# PID.net
KiCad netlist of a schematic drawn in EAGLE
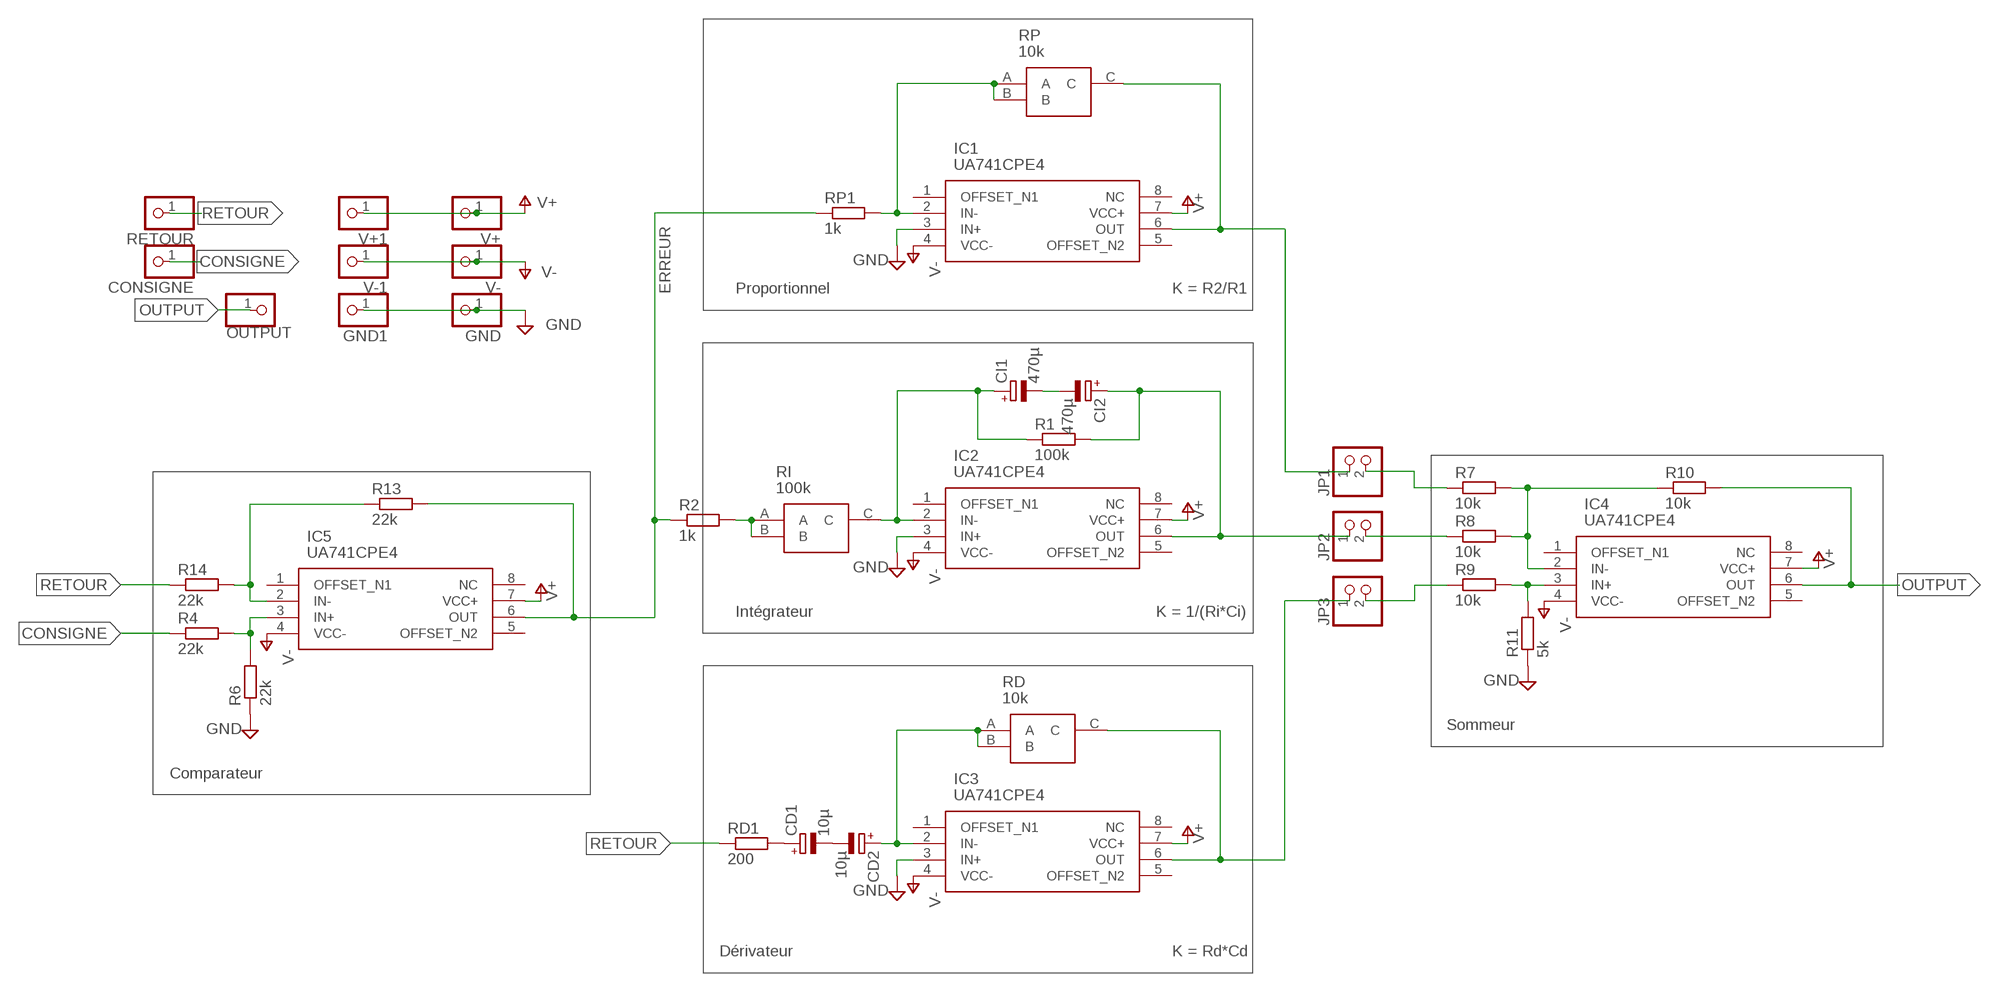
[diagram p0: schematic, sheet 1]

(export (version "E")
  (design (tool "Eeschema 10.0.6"))
  (components
    (comp (ref "CD1")
      (value "10µ")
      (footprint "eagle-import:E2,5-6")
      (libsource (lib "eagle-import") (part "CPOL-EUE2.5-6"))
    )
    (comp (ref "CD2")
      (value "10µ")
      (footprint "eagle-import:E2,5-6")
      (libsource (lib "eagle-import") (part "CPOL-EUE2.5-6"))
    )
    (comp (ref "CI1")
      (value "470µ")
      (footprint "eagle-import:E2,5-6")
      (libsource (lib "eagle-import") (part "CPOL-EUE2.5-6"))
    )
    (comp (ref "CI2")
      (value "470µ")
      (footprint "eagle-import:E2,5-6")
      (libsource (lib "eagle-import") (part "CPOL-EUE2.5-6"))
    )
    (comp (ref "CONSIGNE")
      (value "PINHD-1X1")
      (footprint "eagle-import:1X01")
      (libsource (lib "eagle-import") (part "PINHD-1X1"))
    )
    (comp (ref "GND")
      (value "PINHD-1X1")
      (footprint "eagle-import:1X01")
      (libsource (lib "eagle-import") (part "PINHD-1X1"))
    )
    (comp (ref "GND1")
      (value "PINHD-1X1")
      (footprint "eagle-import:1X01")
      (libsource (lib "eagle-import") (part "PINHD-1X1"))
    )
    (comp (ref "IC1")
      (value "UA741CPE4")
      (footprint "eagle-import:DIP794W53P254L959H508Q8N")
      (fields
        (field (name "MOUSER_PART_NUMBER") "595-UA741CPE4")
        (field (name "SPICEMODEL") "OPAMP")
        (field (name "SPICEPREFIX") "X")
      )
      (libsource (lib "eagle-import") (part "UA741CPE4"))
    )
    (comp (ref "IC2")
      (value "UA741CPE4")
      (footprint "eagle-import:DIP794W53P254L959H508Q8N")
      (fields
        (field (name "MOUSER_PART_NUMBER") "595-UA741CPE4")
        (field (name "SPICEMODEL") "OPAMP")
        (field (name "SPICEPREFIX") "X")
      )
      (libsource (lib "eagle-import") (part "UA741CPE4"))
    )
    (comp (ref "IC3")
      (value "UA741CPE4")
      (footprint "eagle-import:DIP794W53P254L959H508Q8N")
      (fields
        (field (name "MOUSER_PART_NUMBER") "595-UA741CPE4")
        (field (name "SPICEMODEL") "OPAMP")
        (field (name "SPICEPREFIX") "X")
      )
      (libsource (lib "eagle-import") (part "UA741CPE4"))
    )
    (comp (ref "IC4")
      (value "UA741CPE4")
      (footprint "eagle-import:DIP794W53P254L959H508Q8N")
      (fields
        (field (name "MOUSER_PART_NUMBER") "595-UA741CPE4")
        (field (name "SPICEMODEL") "OPAMP")
        (field (name "SPICEPREFIX") "X")
      )
      (libsource (lib "eagle-import") (part "UA741CPE4"))
    )
    (comp (ref "IC5")
      (value "UA741CPE4")
      (footprint "eagle-import:DIP794W53P254L959H508Q8N")
      (fields
        (field (name "MOUSER_PART_NUMBER") "595-UA741CPE4")
        (field (name "SPICEMODEL") "OPAMP")
        (field (name "SPICEPREFIX") "X")
      )
      (libsource (lib "eagle-import") (part "UA741CPE4"))
    )
    (comp (ref "JP1")
      (value "PINHD-1X2")
      (footprint "eagle-import:1X02")
      (libsource (lib "eagle-import") (part "PINHD-1X2"))
    )
    (comp (ref "JP2")
      (value "PINHD-1X2")
      (footprint "eagle-import:1X02")
      (libsource (lib "eagle-import") (part "PINHD-1X2"))
    )
    (comp (ref "JP3")
      (value "PINHD-1X2")
      (footprint "eagle-import:1X02")
      (libsource (lib "eagle-import") (part "PINHD-1X2"))
    )
    (comp (ref "OUTPUT")
      (value "PINHD-1X1")
      (footprint "eagle-import:1X01")
      (libsource (lib "eagle-import") (part "PINHD-1X1"))
    )
    (comp (ref "R1")
      (value "100k")
      (footprint "eagle-import:0204_7")
      (libsource (lib "eagle-import") (part "R-EU_0204/7"))
    )
    (comp (ref "R2")
      (value "1k")
      (footprint "eagle-import:0204_7")
      (libsource (lib "eagle-import") (part "R-EU_0204/7"))
    )
    (comp (ref "R4")
      (value "22k")
      (footprint "eagle-import:0204_7")
      (libsource (lib "eagle-import") (part "R-EU_0204/7"))
    )
    (comp (ref "R6")
      (value "22k")
      (footprint "eagle-import:0204_7")
      (libsource (lib "eagle-import") (part "R-EU_0204/7"))
    )
    (comp (ref "R7")
      (value "10k")
      (footprint "eagle-import:0204_7")
      (libsource (lib "eagle-import") (part "R-EU_0204/7"))
    )
    (comp (ref "R8")
      (value "10k")
      (footprint "eagle-import:0204_7")
      (libsource (lib "eagle-import") (part "R-EU_0204/7"))
    )
    (comp (ref "R9")
      (value "10k")
      (footprint "eagle-import:0204_7")
      (libsource (lib "eagle-import") (part "R-EU_0204/7"))
    )
    (comp (ref "R10")
      (value "10k")
      (footprint "eagle-import:0204_7")
      (libsource (lib "eagle-import") (part "R-EU_0204/7"))
    )
    (comp (ref "R11")
      (value "5k")
      (footprint "eagle-import:0204_7")
      (libsource (lib "eagle-import") (part "R-EU_0204/7"))
    )
    (comp (ref "R13")
      (value "22k")
      (footprint "eagle-import:0204_7")
      (libsource (lib "eagle-import") (part "R-EU_0204/7"))
    )
    (comp (ref "R14")
      (value "22k")
      (footprint "eagle-import:0204_7")
      (libsource (lib "eagle-import") (part "R-EU_0204/7"))
    )
    (comp (ref "RD")
      (value "10k")
      (footprint "eagle-import:T7YA")
      (fields
        (field (name "MANUFACTURER_PART_NUMBER") "T7YA103MT20")
        (field (name "RS_PART_NUMBER") "3746787P")
      )
      (libsource (lib "eagle-import") (part "T7YA103MT20"))
    )
    (comp (ref "RD1")
      (value "200")
      (footprint "eagle-import:0204_7")
      (libsource (lib "eagle-import") (part "R-EU_0204/7"))
    )
    (comp (ref "RETOUR")
      (value "PINHD-1X1")
      (footprint "eagle-import:1X01")
      (libsource (lib "eagle-import") (part "PINHD-1X1"))
    )
    (comp (ref "RI")
      (value "100k")
      (footprint "eagle-import:T7YA")
      (fields
        (field (name "MANUFACTURER_PART_NUMBER") "T7YA103MT20")
        (field (name "RS_PART_NUMBER") "3746787P")
      )
      (libsource (lib "eagle-import") (part "T7YA103MT20"))
    )
    (comp (ref "RP")
      (value "10k")
      (footprint "eagle-import:T7YA")
      (fields
        (field (name "MANUFACTURER_PART_NUMBER") "T7YA103MT20")
        (field (name "RS_PART_NUMBER") "3746787P")
      )
      (libsource (lib "eagle-import") (part "T7YA103MT20"))
    )
    (comp (ref "RP1")
      (value "1k")
      (footprint "eagle-import:0204_7")
      (libsource (lib "eagle-import") (part "R-EU_0204/7"))
    )
    (comp (ref "V+")
      (value "PINHD-1X1")
      (footprint "eagle-import:1X01")
      (libsource (lib "eagle-import") (part "PINHD-1X1"))
    )
    (comp (ref "V+1")
      (value "PINHD-1X1")
      (footprint "eagle-import:1X01")
      (libsource (lib "eagle-import") (part "PINHD-1X1"))
    )
    (comp (ref "V-")
      (value "PINHD-1X1")
      (footprint "eagle-import:1X01")
      (libsource (lib "eagle-import") (part "PINHD-1X1"))
    )
    (comp (ref "V-1")
      (value "PINHD-1X1")
      (footprint "eagle-import:1X01")
      (libsource (lib "eagle-import") (part "PINHD-1X1"))
    )
  )
  (nets
    (net (code "1") (name "/ERREUR") (class "Default")
      (node (ref "IC5") (pin "6") (pinfunction "OUT_6") (pintype "output"))
      (node (ref "R13") (pin "2") (pinfunction "2_2") (pintype "passive"))
      (node (ref "R2") (pin "1") (pinfunction "1_1") (pintype "passive"))
      (node (ref "RP1") (pin "1") (pinfunction "1_1") (pintype "passive"))
    )
    (net (code "2") (name "CONSIGNE") (class "Default")
      (node (ref "CONSIGNE") (pin "1") (pinfunction "1_1") (pintype "passive"))
      (node (ref "R4") (pin "1") (pinfunction "1_1") (pintype "passive"))
    )
    (net (code "3") (name "GND") (class "Default")
      (node (ref "GND") (pin "1") (pinfunction "1_1") (pintype "passive"))
      (node (ref "GND1") (pin "1") (pinfunction "1_1") (pintype "passive"))
      (node (ref "IC1") (pin "3") (pinfunction "IN+_3") (pintype "input"))
      (node (ref "IC2") (pin "3") (pinfunction "IN+_3") (pintype "input"))
      (node (ref "IC3") (pin "3") (pinfunction "IN+_3") (pintype "input"))
      (node (ref "R11") (pin "1") (pinfunction "1_1") (pintype "passive"))
      (node (ref "R6") (pin "1") (pinfunction "1_1") (pintype "passive"))
    )
    (net (code "4") (name "Net-(CD1-Pad+)") (class "Default")
      (node (ref "CD1") (pin "+") (pinfunction "+_+") (pintype "passive"))
      (node (ref "RD1") (pin "2") (pinfunction "2_2") (pintype "passive"))
    )
    (net (code "5") (name "Net-(CD1-Pad-)") (class "Default")
      (node (ref "CD1") (pin "-") (pinfunction "-_-") (pintype "passive"))
      (node (ref "CD2") (pin "-") (pinfunction "-_-") (pintype "passive"))
    )
    (net (code "6") (name "Net-(CI1-Pad-)") (class "Default")
      (node (ref "CI1") (pin "-") (pinfunction "-_-") (pintype "passive"))
      (node (ref "CI2") (pin "-") (pinfunction "-_-") (pintype "passive"))
    )
    (net (code "7") (name "Net-(IC1-IN-)") (class "Default")
      (node (ref "IC1") (pin "2") (pinfunction "IN-_2") (pintype "input"))
      (node (ref "RP") (pin "A") (pinfunction "A_A") (pintype "bidirectional"))
      (node (ref "RP") (pin "B") (pinfunction "B_B") (pintype "bidirectional"))
      (node (ref "RP1") (pin "2") (pinfunction "2_2") (pintype "passive"))
    )
    (net (code "8") (name "Net-(IC1-OUT)") (class "Default")
      (node (ref "IC1") (pin "6") (pinfunction "OUT_6") (pintype "output"))
      (node (ref "JP1") (pin "1") (pinfunction "1_1") (pintype "passive"))
      (node (ref "RP") (pin "C") (pinfunction "C_C") (pintype "bidirectional"))
    )
    (net (code "9") (name "Net-(IC2-IN-)") (class "Default")
      (node (ref "CI1") (pin "+") (pinfunction "+_+") (pintype "passive"))
      (node (ref "IC2") (pin "2") (pinfunction "IN-_2") (pintype "input"))
      (node (ref "R1") (pin "1") (pinfunction "1_1") (pintype "passive"))
      (node (ref "RI") (pin "C") (pinfunction "C_C") (pintype "bidirectional"))
    )
    (net (code "10") (name "Net-(IC2-OUT)") (class "Default")
      (node (ref "CI2") (pin "+") (pinfunction "+_+") (pintype "passive"))
      (node (ref "IC2") (pin "6") (pinfunction "OUT_6") (pintype "output"))
      (node (ref "JP2") (pin "1") (pinfunction "1_1") (pintype "passive"))
      (node (ref "R1") (pin "2") (pinfunction "2_2") (pintype "passive"))
    )
    (net (code "11") (name "Net-(IC3-IN-)") (class "Default")
      (node (ref "CD2") (pin "+") (pinfunction "+_+") (pintype "passive"))
      (node (ref "IC3") (pin "2") (pinfunction "IN-_2") (pintype "input"))
      (node (ref "RD") (pin "A") (pinfunction "A_A") (pintype "bidirectional"))
      (node (ref "RD") (pin "B") (pinfunction "B_B") (pintype "bidirectional"))
    )
    (net (code "12") (name "Net-(IC3-OUT)") (class "Default")
      (node (ref "IC3") (pin "6") (pinfunction "OUT_6") (pintype "output"))
      (node (ref "JP3") (pin "1") (pinfunction "1_1") (pintype "passive"))
      (node (ref "RD") (pin "C") (pinfunction "C_C") (pintype "bidirectional"))
    )
    (net (code "13") (name "Net-(IC4-IN+)") (class "Default")
      (node (ref "IC4") (pin "3") (pinfunction "IN+_3") (pintype "input"))
      (node (ref "R11") (pin "2") (pinfunction "2_2") (pintype "passive"))
      (node (ref "R9") (pin "2") (pinfunction "2_2") (pintype "passive"))
    )
    (net (code "14") (name "Net-(IC4-IN-)") (class "Default")
      (node (ref "IC4") (pin "2") (pinfunction "IN-_2") (pintype "input"))
      (node (ref "R10") (pin "1") (pinfunction "1_1") (pintype "passive"))
      (node (ref "R7") (pin "2") (pinfunction "2_2") (pintype "passive"))
      (node (ref "R8") (pin "2") (pinfunction "2_2") (pintype "passive"))
    )
    (net (code "15") (name "Net-(IC5-IN+)") (class "Default")
      (node (ref "IC5") (pin "3") (pinfunction "IN+_3") (pintype "input"))
      (node (ref "R4") (pin "2") (pinfunction "2_2") (pintype "passive"))
      (node (ref "R6") (pin "2") (pinfunction "2_2") (pintype "passive"))
    )
    (net (code "16") (name "Net-(IC5-IN-)") (class "Default")
      (node (ref "IC5") (pin "2") (pinfunction "IN-_2") (pintype "input"))
      (node (ref "R13") (pin "1") (pinfunction "1_1") (pintype "passive"))
      (node (ref "R14") (pin "2") (pinfunction "2_2") (pintype "passive"))
    )
    (net (code "17") (name "Net-(JP1-Pad2)") (class "Default")
      (node (ref "JP1") (pin "2") (pinfunction "2_2") (pintype "passive"))
      (node (ref "R7") (pin "1") (pinfunction "1_1") (pintype "passive"))
    )
    (net (code "18") (name "Net-(JP2-Pad2)") (class "Default")
      (node (ref "JP2") (pin "2") (pinfunction "2_2") (pintype "passive"))
      (node (ref "R8") (pin "1") (pinfunction "1_1") (pintype "passive"))
    )
    (net (code "19") (name "Net-(JP3-Pad2)") (class "Default")
      (node (ref "JP3") (pin "2") (pinfunction "2_2") (pintype "passive"))
      (node (ref "R9") (pin "1") (pinfunction "1_1") (pintype "passive"))
    )
    (net (code "20") (name "Net-(R2-Pad2)") (class "Default")
      (node (ref "R2") (pin "2") (pinfunction "2_2") (pintype "passive"))
      (node (ref "RI") (pin "A") (pinfunction "A_A") (pintype "bidirectional"))
      (node (ref "RI") (pin "B") (pinfunction "B_B") (pintype "bidirectional"))
    )
    (net (code "21") (name "OUTPUT") (class "Default")
      (node (ref "IC4") (pin "6") (pinfunction "OUT_6") (pintype "output"))
      (node (ref "OUTPUT") (pin "1") (pinfunction "1_1") (pintype "passive"))
      (node (ref "R10") (pin "2") (pinfunction "2_2") (pintype "passive"))
    )
    (net (code "22") (name "RETOUR") (class "Default")
      (node (ref "R14") (pin "1") (pinfunction "1_1") (pintype "passive"))
      (node (ref "RD1") (pin "1") (pinfunction "1_1") (pintype "passive"))
      (node (ref "RETOUR") (pin "1") (pinfunction "1_1") (pintype "passive"))
    )
    (net (code "23") (name "V+") (class "Default")
      (node (ref "IC1") (pin "7") (pinfunction "VCC+_7") (pintype "power_in"))
      (node (ref "IC2") (pin "7") (pinfunction "VCC+_7") (pintype "power_in"))
      (node (ref "IC3") (pin "7") (pinfunction "VCC+_7") (pintype "power_in"))
      (node (ref "IC4") (pin "7") (pinfunction "VCC+_7") (pintype "power_in"))
      (node (ref "IC5") (pin "7") (pinfunction "VCC+_7") (pintype "power_in"))
      (node (ref "V+") (pin "1") (pinfunction "1_1") (pintype "passive"))
      (node (ref "V+1") (pin "1") (pinfunction "1_1") (pintype "passive"))
    )
    (net (code "24") (name "V-") (class "Default")
      (node (ref "IC1") (pin "4") (pinfunction "VCC-_4") (pintype "power_in"))
      (node (ref "IC2") (pin "4") (pinfunction "VCC-_4") (pintype "power_in"))
      (node (ref "IC3") (pin "4") (pinfunction "VCC-_4") (pintype "power_in"))
      (node (ref "IC4") (pin "4") (pinfunction "VCC-_4") (pintype "power_in"))
      (node (ref "IC5") (pin "4") (pinfunction "VCC-_4") (pintype "power_in"))
      (node (ref "V-") (pin "1") (pinfunction "1_1") (pintype "passive"))
      (node (ref "V-1") (pin "1") (pinfunction "1_1") (pintype "passive"))
    )
    (net (code "25") (name "unconnected-(IC1-NC-Pad8)") (class "Default")
      (node (ref "IC1") (pin "8") (pinfunction "NC_8") (pintype "no_connect"))
    )
    (net (code "26") (name "unconnected-(IC1-OFFSET_N1-Pad1)") (class "Default")
      (node (ref "IC1") (pin "1") (pinfunction "OFFSET_N1_1") (pintype "bidirectional"))
    )
    (net (code "27") (name "unconnected-(IC1-OFFSET_N2-Pad5)") (class "Default")
      (node (ref "IC1") (pin "5") (pinfunction "OFFSET_N2_5") (pintype "bidirectional"))
    )
    (net (code "28") (name "unconnected-(IC2-NC-Pad8)") (class "Default")
      (node (ref "IC2") (pin "8") (pinfunction "NC_8") (pintype "no_connect"))
    )
    (net (code "29") (name "unconnected-(IC2-OFFSET_N1-Pad1)") (class "Default")
      (node (ref "IC2") (pin "1") (pinfunction "OFFSET_N1_1") (pintype "bidirectional"))
    )
    (net (code "30") (name "unconnected-(IC2-OFFSET_N2-Pad5)") (class "Default")
      (node (ref "IC2") (pin "5") (pinfunction "OFFSET_N2_5") (pintype "bidirectional"))
    )
    (net (code "31") (name "unconnected-(IC3-NC-Pad8)") (class "Default")
      (node (ref "IC3") (pin "8") (pinfunction "NC_8") (pintype "no_connect"))
    )
    (net (code "32") (name "unconnected-(IC3-OFFSET_N1-Pad1)") (class "Default")
      (node (ref "IC3") (pin "1") (pinfunction "OFFSET_N1_1") (pintype "bidirectional"))
    )
    (net (code "33") (name "unconnected-(IC3-OFFSET_N2-Pad5)") (class "Default")
      (node (ref "IC3") (pin "5") (pinfunction "OFFSET_N2_5") (pintype "bidirectional"))
    )
    (net (code "34") (name "unconnected-(IC4-NC-Pad8)") (class "Default")
      (node (ref "IC4") (pin "8") (pinfunction "NC_8") (pintype "no_connect"))
    )
    (net (code "35") (name "unconnected-(IC4-OFFSET_N1-Pad1)") (class "Default")
      (node (ref "IC4") (pin "1") (pinfunction "OFFSET_N1_1") (pintype "bidirectional"))
    )
    (net (code "36") (name "unconnected-(IC4-OFFSET_N2-Pad5)") (class "Default")
      (node (ref "IC4") (pin "5") (pinfunction "OFFSET_N2_5") (pintype "bidirectional"))
    )
    (net (code "37") (name "unconnected-(IC5-NC-Pad8)") (class "Default")
      (node (ref "IC5") (pin "8") (pinfunction "NC_8") (pintype "no_connect"))
    )
    (net (code "38") (name "unconnected-(IC5-OFFSET_N1-Pad1)") (class "Default")
      (node (ref "IC5") (pin "1") (pinfunction "OFFSET_N1_1") (pintype "bidirectional"))
    )
    (net (code "39") (name "unconnected-(IC5-OFFSET_N2-Pad5)") (class "Default")
      (node (ref "IC5") (pin "5") (pinfunction "OFFSET_N2_5") (pintype "bidirectional"))
    )
  )
)
